# mini.net
KiCad netlist of a schematic drawn in Altium Designer
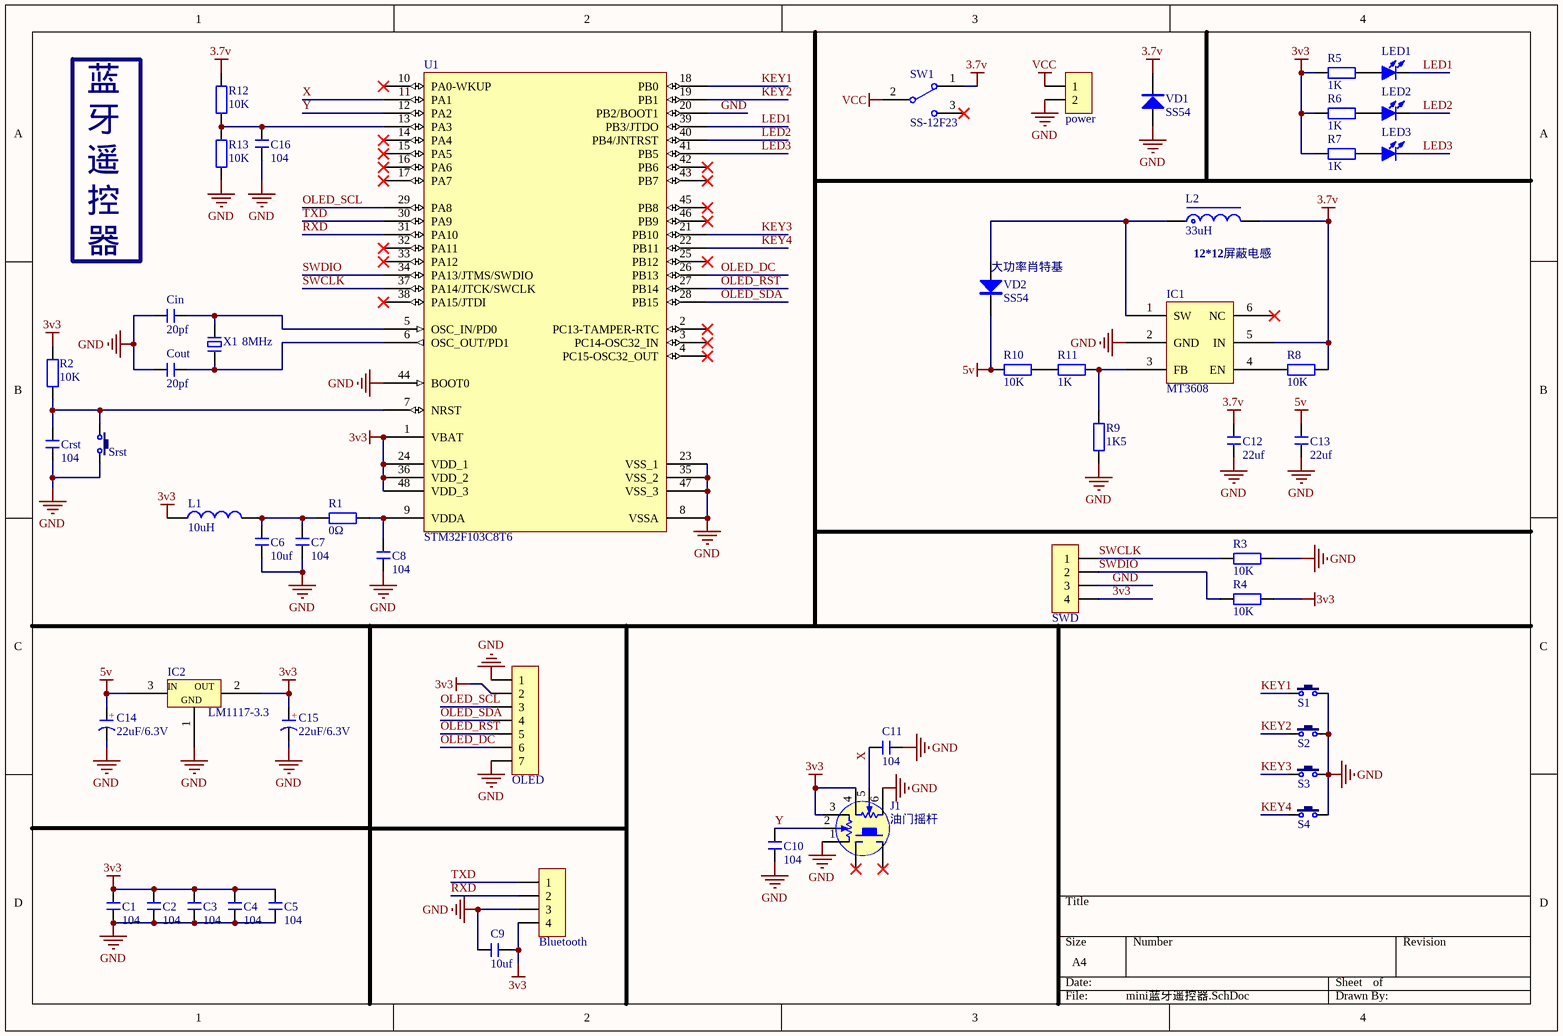
[diagram p0: mini蓝牙遥控器.SchDoc]

(export (version "E")
  (design (tool "Eeschema 10.0.6"))
  (components
    (comp (ref "Bluetooth")
      (value "HDR-1X4")
      (footprint "HDR-1X4")
      (description "4P接插件")
      (fields (field (name "版权归属") "源创客"))
      (libsource (lib "") (part "Header 4_1"))
    )
    (comp (ref "C1")
      (value "104")
      (footprint "C 0603")
      (description "无极性贴片电容")
      (fields (field (name "版权归属") "源创客"))
      (libsource (lib "电阻-电容-电感") (part "C"))
    )
    (comp (ref "C2")
      (value "104")
      (footprint "C 0603")
      (description "无极性贴片电容")
      (fields (field (name "版权归属") "源创客"))
      (libsource (lib "电阻-电容-电感") (part "C"))
    )
    (comp (ref "C3")
      (value "104")
      (footprint "C 0603")
      (description "无极性贴片电容")
      (fields (field (name "版权归属") "源创客"))
      (libsource (lib "电阻-电容-电感") (part "C"))
    )
    (comp (ref "C4")
      (value "104")
      (footprint "C 0603")
      (description "无极性贴片电容")
      (fields (field (name "版权归属") "源创客"))
      (libsource (lib "电阻-电容-电感") (part "C"))
    )
    (comp (ref "C5")
      (value "104")
      (footprint "C 0603")
      (description "无极性贴片电容")
      (fields (field (name "版权归属") "源创客"))
      (libsource (lib "电阻-电容-电感") (part "C"))
    )
    (comp (ref "C6")
      (value "10uf")
      (footprint "C 0603")
      (description "无极性贴片电容")
      (fields (field (name "版权归属") "源创客"))
      (libsource (lib "电阻-电容-电感") (part "C"))
    )
    (comp (ref "C7")
      (value "104")
      (footprint "C 0603")
      (description "无极性贴片电容")
      (fields (field (name "版权归属") "源创客"))
      (libsource (lib "电阻-电容-电感") (part "C"))
    )
    (comp (ref "C8")
      (value "104")
      (footprint "C 0603")
      (description "无极性贴片电容")
      (fields (field (name "版权归属") "源创客"))
      (libsource (lib "电阻-电容-电感") (part "C"))
    )
    (comp (ref "C9")
      (value "10uf")
      (footprint "C 0603")
      (description "无极性贴片电容")
      (fields (field (name "版权归属") "源创客"))
      (libsource (lib "电阻-电容-电感") (part "C"))
    )
    (comp (ref "C10")
      (value "104")
      (footprint "C 0603")
      (description "无极性贴片电容")
      (fields (field (name "版权归属") "源创客"))
      (libsource (lib "电阻-电容-电感") (part "C"))
    )
    (comp (ref "C11")
      (value "104")
      (footprint "C 0603")
      (description "无极性贴片电容")
      (fields (field (name "版权归属") "源创客"))
      (libsource (lib "电阻-电容-电感") (part "C"))
    )
    (comp (ref "C12")
      (value "22uf")
      (footprint "C 1206")
      (description "无极性贴片电容")
      (fields (field (name "版权归属") "源创客"))
      (libsource (lib "电阻-电容-电感") (part "C"))
    )
    (comp (ref "C13")
      (value "22uf")
      (footprint "C 1206")
      (description "无极性贴片电容")
      (fields (field (name "版权归属") "源创客"))
      (libsource (lib "电阻-电容-电感") (part "C"))
    )
    (comp (ref "C14")
      (value "22uF/6.3V")
      (footprint "CD A(3216)")
      (description "贴片钽电容")
      (fields (field (name "版权归属") "源创客"))
      (libsource (lib "电阻-电容-电感") (part "C-CD"))
    )
    (comp (ref "C15")
      (value "22uF/6.3V")
      (footprint "CD A(3216)")
      (description "贴片钽电容")
      (fields (field (name "版权归属") "源创客"))
      (libsource (lib "电阻-电容-电感") (part "C-CD"))
    )
    (comp (ref "C16")
      (value "104")
      (footprint "C 0603")
      (description "无极性贴片电容")
      (fields (field (name "版权归属") "源创客"))
      (libsource (lib "电阻-电容-电感") (part "C"))
    )
    (comp (ref "Cin")
      (value "20pf")
      (footprint "C 0603")
      (description "无极性贴片电容")
      (fields (field (name "版权归属") "源创客"))
      (libsource (lib "电阻-电容-电感") (part "C"))
    )
    (comp (ref "Cout")
      (value "20pf")
      (footprint "C 0603")
      (description "无极性贴片电容")
      (fields (field (name "版权归属") "源创客"))
      (libsource (lib "电阻-电容-电感") (part "C"))
    )
    (comp (ref "Crst")
      (value "104")
      (footprint "C 0603")
      (description "无极性贴片电容")
      (fields (field (name "版权归属") "源创客"))
      (libsource (lib "电阻-电容-电感") (part "C"))
    )
    (comp (ref "IC1") (value "MT3608") (footprint "SOT23-6L") (libsource (lib "MT3608") (part "Component_1")))
    (comp (ref "IC2")
      (value "LM1117-3.3")
      (footprint "SOT223_L")
      (libsource (lib "PackageXu") (part "AMS1117"))
    )
    (comp (ref "J1")
      (value "油门摇杆")
      (footprint "摇杆2")
      (description "摇杆")
      (libsource (lib "REMOTOR V1.6") (part "摇杆"))
    )
    (comp (ref "L1")
      (value "10uH")
      (footprint "L 0603")
      (description "小功率贴片电感")
      (fields (field (name "版权归属") "源创客"))
      (libsource (lib "电阻-电容-电感") (part "L"))
    )
    (comp (ref "L2")
      (value "33uH")
      (footprint "CD54")
      (description "贴片功率电感")
      (fields (field (name "版权归属") "源创客"))
      (libsource (lib "电阻-电容-电感") (part "L-CD"))
    )
    (comp (ref "LED1")
      (value "红色")
      (footprint "LED 0603R")
      (description "贴片LED")
      (fields (field (name "版权归属") "源创客"))
      (libsource (lib "LED") (part "LED-SMD"))
    )
    (comp (ref "LED2")
      (value "红色")
      (footprint "LED 0603B")
      (description "贴片LED")
      (fields (field (name "版权归属") "源创客"))
      (libsource (lib "LED") (part "LED-SMD"))
    )
    (comp (ref "LED3")
      (value "红色")
      (footprint "LED 0603G")
      (description "贴片LED")
      (fields (field (name "版权归属") "源创客"))
      (libsource (lib "LED") (part "LED-SMD"))
    )
    (comp (ref "OLED")
      (value "HDR-1X7")
      (footprint "HDR-1X7")
      (description "7P接插件")
      (fields (field (name "版权归属") "源创客"))
      (libsource (lib "接插件") (part "Header 7"))
    )
    (comp (ref "power")
      (value "HDR-1X2")
      (footprint "HDR-1X2")
      (description "2P接插件")
      (fields (field (name "版权归属") "源创客"))
      (libsource (lib "接插件") (part "Header 2"))
    )
    (comp (ref "R1")
      (value "0Ω")
      (footprint "R 0603")
      (description "贴片电阻")
      (fields (field (name "版权归属") "源创客"))
      (libsource (lib "电阻-电容-电感") (part "R"))
    )
    (comp (ref "R2")
      (value "10K")
      (footprint "R 0603")
      (description "贴片电阻")
      (fields (field (name "版权归属") "源创客"))
      (libsource (lib "电阻-电容-电感") (part "R"))
    )
    (comp (ref "R3")
      (value "10K")
      (footprint "R 0603")
      (description "贴片电阻")
      (fields (field (name "版权归属") "源创客"))
      (libsource (lib "电阻-电容-电感") (part "R"))
    )
    (comp (ref "R4")
      (value "10K")
      (footprint "R 0603")
      (description "贴片电阻")
      (fields (field (name "版权归属") "源创客"))
      (libsource (lib "电阻-电容-电感") (part "R"))
    )
    (comp (ref "R5")
      (value "1K")
      (footprint "R 0603")
      (description "贴片电阻")
      (fields (field (name "版权归属") "源创客"))
      (libsource (lib "电阻-电容-电感") (part "R"))
    )
    (comp (ref "R6")
      (value "1K")
      (footprint "R 0603")
      (description "贴片电阻")
      (fields (field (name "版权归属") "源创客"))
      (libsource (lib "电阻-电容-电感") (part "R"))
    )
    (comp (ref "R7")
      (value "1K")
      (footprint "R 0603")
      (description "贴片电阻")
      (fields (field (name "版权归属") "源创客"))
      (libsource (lib "电阻-电容-电感") (part "R"))
    )
    (comp (ref "R8")
      (value "10K")
      (footprint "R 0603")
      (description "贴片电阻")
      (fields (field (name "版权归属") "源创客"))
      (libsource (lib "电阻-电容-电感") (part "R"))
    )
    (comp (ref "R9")
      (value "1K5")
      (footprint "R 0603")
      (description "贴片电阻")
      (fields (field (name "版权归属") "源创客"))
      (libsource (lib "电阻-电容-电感") (part "R"))
    )
    (comp (ref "R10")
      (value "10K")
      (footprint "R 0603")
      (description "贴片电阻")
      (fields (field (name "版权归属") "源创客"))
      (libsource (lib "电阻-电容-电感") (part "R"))
    )
    (comp (ref "R11")
      (value "1K")
      (footprint "R 0603")
      (description "贴片电阻")
      (fields (field (name "版权归属") "源创客"))
      (libsource (lib "电阻-电容-电感") (part "R"))
    )
    (comp (ref "R12")
      (value "10K")
      (footprint "R 0603")
      (description "贴片电阻")
      (fields (field (name "版权归属") "源创客"))
      (libsource (lib "电阻-电容-电感") (part "R"))
    )
    (comp (ref "R13")
      (value "10K")
      (footprint "R 0603")
      (description "贴片电阻")
      (fields (field (name "版权归属") "源创客"))
      (libsource (lib "电阻-电容-电感") (part "R"))
    )
    (comp (ref "S1")
      (value "3x6x5")
      (footprint "TSW SMD-3*6*2.5")
      (description "3x6轻触开关")
      (fields (field (name "版权归属") "源创客"))
      (libsource (lib "按键-开关") (part "TSW 3x6"))
    )
    (comp (ref "S2")
      (value "3x6x5")
      (footprint "TSW SMD-3*6*2.5")
      (description "3x6轻触开关")
      (fields (field (name "版权归属") "源创客"))
      (libsource (lib "按键-开关") (part "TSW 3x6"))
    )
    (comp (ref "S3")
      (value "3x6x5")
      (footprint "TSW SMD-3*6*2.5")
      (description "3x6轻触开关")
      (fields (field (name "版权归属") "源创客"))
      (libsource (lib "按键-开关") (part "TSW 3x6"))
    )
    (comp (ref "S4")
      (value "3x6x5")
      (footprint "TSW SMD-3*6*2.5")
      (description "3x6轻触开关")
      (fields (field (name "版权归属") "源创客"))
      (libsource (lib "按键-开关") (part "TSW 3x6"))
    )
    (comp (ref "Srst")
      (value "3x6x5")
      (footprint "TSW SMD-3*6*2.5")
      (description "3x6轻触开关")
      (fields (field (name "版权归属") "源创客"))
      (libsource (lib "按键-开关") (part "TSW 3x6"))
    )
    (comp (ref "SW1")
      (value "SS-12F23")
      (footprint "MSK-12C01-07")
      (description "1路波动开关")
      (fields (field (name "版权归属") "源创客"))
      (libsource (lib "按键-开关") (part "SSW-1P"))
    )
    (comp (ref "SWD")
      (value "HDR-1X4")
      (footprint "HDR-1X4")
      (description "4P接插件")
      (fields (field (name "版权归属") "源创客"))
      (libsource (lib "接插件") (part "Header 4"))
    )
    (comp (ref "U1")
      (value "STM32F103C8T6")
      (footprint "LQFP48 7X7_M")
      (description "Flaah:64/RAM:20/IO:36")
      (fields (field (name "版权归属") "源创客"))
      (libsource (lib "STM32系列单片机") (part "STM32F103C8T6"))
    )
    (comp (ref "VD1")
      (value "SS54")
      (footprint "SMA")
      (description "肖特基二极管")
      (fields (field (name "版权归属") "源创客"))
      (libsource (lib "二极管-整流桥") (part "SS14"))
    )
    (comp (ref "VD2")
      (value "SS54")
      (footprint "SMA")
      (description "肖特基二极管")
      (fields (field (name "版权归属") "源创客"))
      (libsource (lib "二极管-整流桥") (part "SS14"))
    )
    (comp (ref "X1")
      (value "8MHz")
      (footprint "LC-SMD-5032_2P")
      (description "2脚晶振")
      (fields (field (name "版权归属") "源创客"))
      (libsource (lib "保险丝-晶振") (part "XTAL-2"))
    )
  )
  (nets
    (net (code "1") (name "/KEY1") (class "Default")
      (node (ref "S1") (pin "1") (pinfunction "1_1") (pintype "passive"))
      (node (ref "U1") (pin "18") (pinfunction "PB0_18") (pintype "bidirectional"))
    )
    (net (code "2") (name "/KEY2") (class "Default")
      (node (ref "S2") (pin "1") (pinfunction "1_1") (pintype "passive"))
      (node (ref "U1") (pin "19") (pinfunction "PB1_19") (pintype "bidirectional"))
    )
    (net (code "3") (name "/KEY3") (class "Default")
      (node (ref "S3") (pin "1") (pinfunction "1_1") (pintype "passive"))
      (node (ref "U1") (pin "21") (pinfunction "PB10_21") (pintype "bidirectional"))
    )
    (net (code "4") (name "/KEY4") (class "Default")
      (node (ref "S4") (pin "1") (pinfunction "1_1") (pintype "passive"))
      (node (ref "U1") (pin "22") (pinfunction "PB11_22") (pintype "bidirectional"))
    )
    (net (code "5") (name "/LED1") (class "Default")
      (node (ref "LED1") (pin "2") (pinfunction "K_2") (pintype "passive"))
      (node (ref "U1") (pin "39") (pinfunction "PB3/JTDO_39") (pintype "bidirectional"))
    )
    (net (code "6") (name "/LED2") (class "Default")
      (node (ref "LED2") (pin "2") (pinfunction "K_2") (pintype "passive"))
      (node (ref "U1") (pin "40") (pinfunction "PB4/JNTRST_40") (pintype "bidirectional"))
    )
    (net (code "7") (name "/LED3") (class "Default")
      (node (ref "LED3") (pin "2") (pinfunction "K_2") (pintype "passive"))
      (node (ref "U1") (pin "41") (pinfunction "PB5_41") (pintype "bidirectional"))
    )
    (net (code "8") (name "/OLED_DC") (class "Default")
      (node (ref "OLED") (pin "6") (pinfunction "6_6") (pintype "passive"))
      (node (ref "U1") (pin "26") (pinfunction "PB13_26") (pintype "bidirectional"))
    )
    (net (code "9") (name "/OLED_RST") (class "Default")
      (node (ref "OLED") (pin "5") (pinfunction "5_5") (pintype "passive"))
      (node (ref "U1") (pin "27") (pinfunction "PB14_27") (pintype "bidirectional"))
    )
    (net (code "10") (name "/OLED_SCL") (class "Default")
      (node (ref "OLED") (pin "3") (pinfunction "3_3") (pintype "passive"))
      (node (ref "U1") (pin "29") (pinfunction "PA8_29") (pintype "bidirectional"))
    )
    (net (code "11") (name "/OLED_SDA") (class "Default")
      (node (ref "OLED") (pin "4") (pinfunction "4_4") (pintype "passive"))
      (node (ref "U1") (pin "28") (pinfunction "PB15_28") (pintype "bidirectional"))
    )
    (net (code "12") (name "/RXD") (class "Default")
      (node (ref "Bluetooth") (pin "2") (pinfunction "2_2") (pintype "passive"))
      (node (ref "U1") (pin "31") (pinfunction "PA10_31") (pintype "bidirectional"))
    )
    (net (code "13") (name "/SWCLK") (class "Default")
      (node (ref "R3") (pin "2") (pinfunction "2_2") (pintype "passive"))
      (node (ref "SWD") (pin "1") (pinfunction "1_1") (pintype "passive"))
      (node (ref "U1") (pin "37") (pinfunction "PA14/JTCK/SWCLK_37") (pintype "bidirectional"))
    )
    (net (code "14") (name "/SWDIO") (class "Default")
      (node (ref "R4") (pin "2") (pinfunction "2_2") (pintype "passive"))
      (node (ref "SWD") (pin "2") (pinfunction "2_2") (pintype "passive"))
      (node (ref "U1") (pin "34") (pinfunction "PA13/JTMS/SWDIO_34") (pintype "bidirectional"))
    )
    (net (code "15") (name "/TXD") (class "Default")
      (node (ref "Bluetooth") (pin "1") (pinfunction "1_1") (pintype "passive"))
      (node (ref "U1") (pin "30") (pinfunction "PA9_30") (pintype "bidirectional"))
    )
    (net (code "16") (name "/X") (class "Default")
      (node (ref "C11") (pin "1") (pinfunction "1_1") (pintype "passive"))
      (node (ref "J1") (pin "5") (pinfunction "5_5") (pintype "passive"))
      (node (ref "U1") (pin "11") (pinfunction "PA1_11") (pintype "bidirectional"))
    )
    (net (code "17") (name "/Y") (class "Default")
      (node (ref "C10") (pin "1") (pinfunction "1_1") (pintype "passive"))
      (node (ref "J1") (pin "2") (pinfunction "2_2") (pintype "passive"))
      (node (ref "U1") (pin "12") (pinfunction "PA2_12") (pintype "bidirectional"))
    )
    (net (code "18") (name "3.7v") (class "Default")
      (node (ref "C12") (pin "1") (pinfunction "1_1") (pintype "passive"))
      (node (ref "IC1") (pin "5") (pinfunction "IN_5") (pintype "passive"))
      (node (ref "L2") (pin "2") (pinfunction "2_2") (pintype "passive"))
      (node (ref "R12") (pin "2") (pinfunction "2_2") (pintype "passive"))
      (node (ref "R8") (pin "2") (pinfunction "2_2") (pintype "passive"))
      (node (ref "SW1") (pin "1") (pinfunction "1_1") (pintype "passive"))
      (node (ref "VD1") (pin "2") (pinfunction "K_2") (pintype "passive"))
    )
    (net (code "19") (name "3v3") (class "Default")
      (node (ref "Bluetooth") (pin "4") (pinfunction "4_4") (pintype "passive"))
      (node (ref "C1") (pin "2") (pinfunction "2_2") (pintype "passive"))
      (node (ref "C15") (pin "1") (pinfunction "A_1") (pintype "passive"))
      (node (ref "C2") (pin "2") (pinfunction "2_2") (pintype "passive"))
      (node (ref "C3") (pin "2") (pinfunction "2_2") (pintype "passive"))
      (node (ref "C4") (pin "2") (pinfunction "2_2") (pintype "passive"))
      (node (ref "C5") (pin "2") (pinfunction "2_2") (pintype "passive"))
      (node (ref "C9") (pin "2") (pinfunction "2_2") (pintype "passive"))
      (node (ref "IC2") (pin "2") (pinfunction "OUT_2") (pintype "passive"))
      (node (ref "J1") (pin "3") (pinfunction "3_3") (pintype "passive"))
      (node (ref "J1") (pin "4") (pinfunction "4_4") (pintype "passive"))
      (node (ref "L1") (pin "2") (pinfunction "2_2") (pintype "passive"))
      (node (ref "OLED") (pin "2") (pinfunction "2_2") (pintype "passive"))
      (node (ref "R2") (pin "1") (pinfunction "1_1") (pintype "passive"))
      (node (ref "R4") (pin "1") (pinfunction "1_1") (pintype "passive"))
      (node (ref "R5") (pin "2") (pinfunction "2_2") (pintype "passive"))
      (node (ref "R6") (pin "2") (pinfunction "2_2") (pintype "passive"))
      (node (ref "R7") (pin "2") (pinfunction "2_2") (pintype "passive"))
      (node (ref "SWD") (pin "4") (pinfunction "4_4") (pintype "passive"))
      (node (ref "U1") (pin "1") (pinfunction "VBAT_1") (pintype "power_in"))
      (node (ref "U1") (pin "24") (pinfunction "VDD_1_24") (pintype "power_in"))
      (node (ref "U1") (pin "36") (pinfunction "VDD_2_36") (pintype "power_in"))
      (node (ref "U1") (pin "48") (pinfunction "VDD_3_48") (pintype "power_in"))
    )
    (net (code "20") (name "5v") (class "Default")
      (node (ref "C13") (pin "1") (pinfunction "1_1") (pintype "passive"))
      (node (ref "C14") (pin "1") (pinfunction "A_1") (pintype "passive"))
      (node (ref "IC2") (pin "3") (pinfunction "IN_3") (pintype "passive"))
      (node (ref "R10") (pin "2") (pinfunction "2_2") (pintype "passive"))
      (node (ref "VD2") (pin "2") (pinfunction "K_2") (pintype "passive"))
    )
    (net (code "21") (name "GND") (class "Default")
      (node (ref "Bluetooth") (pin "3") (pinfunction "3_3") (pintype "passive"))
      (node (ref "C1") (pin "1") (pinfunction "1_1") (pintype "passive"))
      (node (ref "C10") (pin "2") (pinfunction "2_2") (pintype "passive"))
      (node (ref "C11") (pin "2") (pinfunction "2_2") (pintype "passive"))
      (node (ref "C12") (pin "2") (pinfunction "2_2") (pintype "passive"))
      (node (ref "C13") (pin "2") (pinfunction "2_2") (pintype "passive"))
      (node (ref "C14") (pin "2") (pinfunction "K_2") (pintype "passive"))
      (node (ref "C15") (pin "2") (pinfunction "K_2") (pintype "passive"))
      (node (ref "C16") (pin "2") (pinfunction "2_2") (pintype "passive"))
      (node (ref "C2") (pin "1") (pinfunction "1_1") (pintype "passive"))
      (node (ref "C3") (pin "1") (pinfunction "1_1") (pintype "passive"))
      (node (ref "C4") (pin "1") (pinfunction "1_1") (pintype "passive"))
      (node (ref "C5") (pin "1") (pinfunction "1_1") (pintype "passive"))
      (node (ref "C6") (pin "1") (pinfunction "1_1") (pintype "passive"))
      (node (ref "C7") (pin "1") (pinfunction "1_1") (pintype "passive"))
      (node (ref "C8") (pin "1") (pinfunction "1_1") (pintype "passive"))
      (node (ref "C9") (pin "1") (pinfunction "1_1") (pintype "passive"))
      (node (ref "Cin") (pin "1") (pinfunction "1_1") (pintype "passive"))
      (node (ref "Cout") (pin "1") (pinfunction "1_1") (pintype "passive"))
      (node (ref "Crst") (pin "2") (pinfunction "2_2") (pintype "passive"))
      (node (ref "IC1") (pin "2") (pinfunction "GND_2") (pintype "passive"))
      (node (ref "IC2") (pin "1") (pinfunction "149_1") (pintype "passive"))
      (node (ref "J1") (pin "1") (pinfunction "1_1") (pintype "passive"))
      (node (ref "J1") (pin "6") (pinfunction "6_6") (pintype "passive"))
      (node (ref "OLED") (pin "1") (pinfunction "1_1") (pintype "passive"))
      (node (ref "OLED") (pin "7") (pinfunction "7_7") (pintype "passive"))
      (node (ref "R13") (pin "1") (pinfunction "1_1") (pintype "passive"))
      (node (ref "R3") (pin "1") (pinfunction "1_1") (pintype "passive"))
      (node (ref "R9") (pin "1") (pinfunction "1_1") (pintype "passive"))
      (node (ref "S1") (pin "2") (pinfunction "2_2") (pintype "passive"))
      (node (ref "S2") (pin "2") (pinfunction "2_2") (pintype "passive"))
      (node (ref "S3") (pin "2") (pinfunction "2_2") (pintype "passive"))
      (node (ref "S4") (pin "2") (pinfunction "2_2") (pintype "passive"))
      (node (ref "SWD") (pin "3") (pinfunction "3_3") (pintype "passive"))
      (node (ref "Srst") (pin "1") (pinfunction "1_1") (pintype "passive"))
      (node (ref "U1") (pin "20") (pinfunction "PB2/BOOT1_20") (pintype "bidirectional"))
      (node (ref "U1") (pin "23") (pinfunction "VSS_1_23") (pintype "power_in"))
      (node (ref "U1") (pin "35") (pinfunction "VSS_2_35") (pintype "power_in"))
      (node (ref "U1") (pin "44") (pinfunction "BOOT0_44") (pintype "input"))
      (node (ref "U1") (pin "47") (pinfunction "VSS_3_47") (pintype "power_in"))
      (node (ref "U1") (pin "8") (pinfunction "VSSA_8") (pintype "power_in"))
      (node (ref "VD1") (pin "1") (pinfunction "A_1") (pintype "passive"))
      (node (ref "power") (pin "2") (pinfunction "2_2") (pintype "passive"))
    )
    (net (code "22") (name "Net-(C6-Pad2)") (class "Default")
      (node (ref "C6") (pin "2") (pinfunction "2_2") (pintype "passive"))
      (node (ref "C7") (pin "2") (pinfunction "2_2") (pintype "passive"))
      (node (ref "L1") (pin "1") (pinfunction "1_1") (pintype "passive"))
      (node (ref "R1") (pin "2") (pinfunction "2_2") (pintype "passive"))
    )
    (net (code "23") (name "Net-(IC1-EN)") (class "Default")
      (node (ref "IC1") (pin "4") (pinfunction "EN_4") (pintype "passive"))
      (node (ref "R8") (pin "1") (pinfunction "1_1") (pintype "passive"))
    )
    (net (code "24") (name "Net-(IC1-FB)") (class "Default")
      (node (ref "IC1") (pin "3") (pinfunction "FB_3") (pintype "passive"))
      (node (ref "R11") (pin "1") (pinfunction "1_1") (pintype "passive"))
      (node (ref "R9") (pin "2") (pinfunction "2_2") (pintype "passive"))
    )
    (net (code "25") (name "Net-(IC1-SW)") (class "Default")
      (node (ref "IC1") (pin "1") (pinfunction "SW_1") (pintype "passive"))
      (node (ref "L2") (pin "1") (pinfunction "1_1") (pintype "passive"))
      (node (ref "VD2") (pin "1") (pinfunction "A_1") (pintype "passive"))
    )
    (net (code "26") (name "Net-(LED1-A)") (class "Default")
      (node (ref "LED1") (pin "1") (pinfunction "A_1") (pintype "passive"))
      (node (ref "R5") (pin "1") (pinfunction "1_1") (pintype "passive"))
    )
    (net (code "27") (name "Net-(LED2-A)") (class "Default")
      (node (ref "LED2") (pin "1") (pinfunction "A_1") (pintype "passive"))
      (node (ref "R6") (pin "1") (pinfunction "1_1") (pintype "passive"))
    )
    (net (code "28") (name "Net-(LED3-A)") (class "Default")
      (node (ref "LED3") (pin "1") (pinfunction "A_1") (pintype "passive"))
      (node (ref "R7") (pin "1") (pinfunction "1_1") (pintype "passive"))
    )
    (net (code "29") (name "Net-(R10-Pad1)") (class "Default")
      (node (ref "R10") (pin "1") (pinfunction "1_1") (pintype "passive"))
      (node (ref "R11") (pin "2") (pinfunction "2_2") (pintype "passive"))
    )
    (net (code "30") (name "Net-(U1-NRST)") (class "Default")
      (node (ref "Crst") (pin "1") (pinfunction "1_1") (pintype "passive"))
      (node (ref "R2") (pin "2") (pinfunction "2_2") (pintype "passive"))
      (node (ref "Srst") (pin "2") (pinfunction "2_2") (pintype "passive"))
      (node (ref "U1") (pin "7") (pinfunction "NRST_7") (pintype "bidirectional"))
    )
    (net (code "31") (name "Net-(U1-OSC_IN{slash}PD0)") (class "Default")
      (node (ref "Cin") (pin "2") (pinfunction "2_2") (pintype "passive"))
      (node (ref "U1") (pin "5") (pinfunction "OSC_IN/PD0_5") (pintype "input"))
      (node (ref "X1") (pin "2") (pinfunction "2_2") (pintype "passive"))
    )
    (net (code "32") (name "Net-(U1-OSC_OUT{slash}PD1)") (class "Default")
      (node (ref "Cout") (pin "2") (pinfunction "2_2") (pintype "passive"))
      (node (ref "U1") (pin "6") (pinfunction "OSC_OUT/PD1_6") (pintype "output"))
      (node (ref "X1") (pin "1") (pinfunction "1_1") (pintype "passive"))
    )
    (net (code "33") (name "Net-(U1-PA3)") (class "Default")
      (node (ref "C16") (pin "1") (pinfunction "1_1") (pintype "passive"))
      (node (ref "R12") (pin "1") (pinfunction "1_1") (pintype "passive"))
      (node (ref "R13") (pin "2") (pinfunction "2_2") (pintype "passive"))
      (node (ref "U1") (pin "13") (pinfunction "PA3_13") (pintype "bidirectional"))
    )
    (net (code "34") (name "Net-(U1-VDDA)") (class "Default")
      (node (ref "C8") (pin "2") (pinfunction "2_2") (pintype "passive"))
      (node (ref "R1") (pin "1") (pinfunction "1_1") (pintype "passive"))
      (node (ref "U1") (pin "9") (pinfunction "VDDA_9") (pintype "power_in"))
    )
    (net (code "35") (name "VCC") (class "Default")
      (node (ref "SW1") (pin "2") (pinfunction "2_2") (pintype "passive"))
      (node (ref "power") (pin "1") (pinfunction "1_1") (pintype "passive"))
    )
    (net (code "36") (name "unconnected-(IC1-NC-Pad6)") (class "Default")
      (node (ref "IC1") (pin "6") (pinfunction "NC_6") (pintype "passive+no_connect"))
    )
    (net (code "37") (name "unconnected-(J1-PadJ1)") (class "Default")
      (node (ref "J1") (pin "J1") (pinfunction "J1_J1") (pintype "passive+no_connect"))
    )
    (net (code "38") (name "unconnected-(J1-PadJ2)") (class "Default")
      (node (ref "J1") (pin "J2") (pinfunction "J2_J2") (pintype "passive+no_connect"))
    )
    (net (code "39") (name "unconnected-(SW1-Pad3)") (class "Default")
      (node (ref "SW1") (pin "3") (pinfunction "3_3") (pintype "passive+no_connect"))
    )
    (net (code "40") (name "unconnected-(U1-PA0-WKUP-Pad10)") (class "Default")
      (node (ref "U1") (pin "10") (pinfunction "PA0-WKUP_10") (pintype "bidirectional+no_connect"))
    )
    (net (code "41") (name "unconnected-(U1-PA4-Pad14)") (class "Default")
      (node (ref "U1") (pin "14") (pinfunction "PA4_14") (pintype "bidirectional+no_connect"))
    )
    (net (code "42") (name "unconnected-(U1-PA5-Pad15)") (class "Default")
      (node (ref "U1") (pin "15") (pinfunction "PA5_15") (pintype "bidirectional+no_connect"))
    )
    (net (code "43") (name "unconnected-(U1-PA6-Pad16)") (class "Default")
      (node (ref "U1") (pin "16") (pinfunction "PA6_16") (pintype "bidirectional+no_connect"))
    )
    (net (code "44") (name "unconnected-(U1-PA7-Pad17)") (class "Default")
      (node (ref "U1") (pin "17") (pinfunction "PA7_17") (pintype "bidirectional+no_connect"))
    )
    (net (code "45") (name "unconnected-(U1-PA11-Pad32)") (class "Default")
      (node (ref "U1") (pin "32") (pinfunction "PA11_32") (pintype "bidirectional+no_connect"))
    )
    (net (code "46") (name "unconnected-(U1-PA12-Pad33)") (class "Default")
      (node (ref "U1") (pin "33") (pinfunction "PA12_33") (pintype "bidirectional+no_connect"))
    )
    (net (code "47") (name "unconnected-(U1-PA15{slash}JTDI-Pad38)") (class "Default")
      (node (ref "U1") (pin "38") (pinfunction "PA15/JTDI_38") (pintype "bidirectional+no_connect"))
    )
    (net (code "48") (name "unconnected-(U1-PB6-Pad42)") (class "Default")
      (node (ref "U1") (pin "42") (pinfunction "PB6_42") (pintype "bidirectional+no_connect"))
    )
    (net (code "49") (name "unconnected-(U1-PB7-Pad43)") (class "Default")
      (node (ref "U1") (pin "43") (pinfunction "PB7_43") (pintype "bidirectional+no_connect"))
    )
    (net (code "50") (name "unconnected-(U1-PB8-Pad45)") (class "Default")
      (node (ref "U1") (pin "45") (pinfunction "PB8_45") (pintype "bidirectional+no_connect"))
    )
    (net (code "51") (name "unconnected-(U1-PB9-Pad46)") (class "Default")
      (node (ref "U1") (pin "46") (pinfunction "PB9_46") (pintype "bidirectional+no_connect"))
    )
    (net (code "52") (name "unconnected-(U1-PB12-Pad25)") (class "Default")
      (node (ref "U1") (pin "25") (pinfunction "PB12_25") (pintype "bidirectional+no_connect"))
    )
    (net (code "53") (name "unconnected-(U1-PC13-TAMPER-RTC-Pad2)") (class "Default")
      (node (ref "U1") (pin "2") (pinfunction "PC13-TAMPER-RTC_2") (pintype "bidirectional+no_connect"))
    )
    (net (code "54") (name "unconnected-(U1-PC14-OSC32_IN-Pad3)") (class "Default")
      (node (ref "U1") (pin "3") (pinfunction "PC14-OSC32_IN_3") (pintype "bidirectional+no_connect"))
    )
    (net (code "55") (name "unconnected-(U1-PC15-OSC32_OUT-Pad4)") (class "Default")
      (node (ref "U1") (pin "4") (pinfunction "PC15-OSC32_OUT_4") (pintype "bidirectional+no_connect"))
    )
  )
)
